# rectifier_schematic.net
KiCad netlist of a schematic drawn in EAGLE
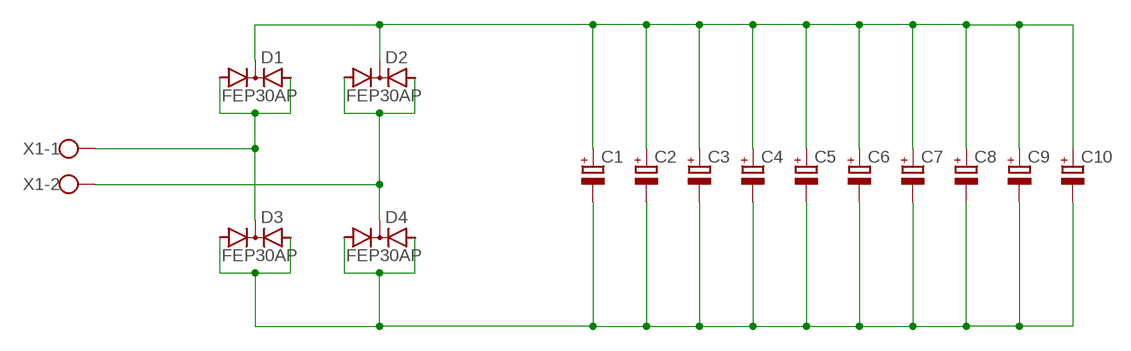
[diagram p0: schematic, sheet 1]

(export (version "E")
  (design (tool "Eeschema 10.0.6"))
  (components
    (comp (ref "C1")
      (value "CPOL-EUE7.5-18")
      (footprint "eagle-import:E7,5-18")
      (libsource (lib "eagle-import") (part "CPOL-EUE7.5-18"))
    )
    (comp (ref "C2")
      (value "CPOL-EUE7.5-18")
      (footprint "eagle-import:E7,5-18")
      (libsource (lib "eagle-import") (part "CPOL-EUE7.5-18"))
    )
    (comp (ref "C3")
      (value "CPOL-EUE7.5-18")
      (footprint "eagle-import:E7,5-18")
      (libsource (lib "eagle-import") (part "CPOL-EUE7.5-18"))
    )
    (comp (ref "C4")
      (value "CPOL-EUE7.5-18")
      (footprint "eagle-import:E7,5-18")
      (libsource (lib "eagle-import") (part "CPOL-EUE7.5-18"))
    )
    (comp (ref "C5")
      (value "CPOL-EUE7.5-18")
      (footprint "eagle-import:E7,5-18")
      (libsource (lib "eagle-import") (part "CPOL-EUE7.5-18"))
    )
    (comp (ref "C6")
      (value "CPOL-EUE7.5-18")
      (footprint "eagle-import:E7,5-18")
      (libsource (lib "eagle-import") (part "CPOL-EUE7.5-18"))
    )
    (comp (ref "C7")
      (value "CPOL-EUE7.5-18")
      (footprint "eagle-import:E7,5-18")
      (libsource (lib "eagle-import") (part "CPOL-EUE7.5-18"))
    )
    (comp (ref "C8")
      (value "CPOL-EUE7.5-18")
      (footprint "eagle-import:E7,5-18")
      (libsource (lib "eagle-import") (part "CPOL-EUE7.5-18"))
    )
    (comp (ref "C9")
      (value "CPOL-EUE7.5-18")
      (footprint "eagle-import:E7,5-18")
      (libsource (lib "eagle-import") (part "CPOL-EUE7.5-18"))
    )
    (comp (ref "C10")
      (value "CPOL-EUE7.5-18")
      (footprint "eagle-import:E7,5-18")
      (libsource (lib "eagle-import") (part "CPOL-EUE7.5-18"))
    )
    (comp (ref "D1")
      (value "FEP30AP")
      (footprint "eagle-import:TO3P")
      (libsource (lib "eagle-import") (part "FEP30AP"))
    )
    (comp (ref "D2")
      (value "FEP30AP")
      (footprint "eagle-import:TO3P")
      (libsource (lib "eagle-import") (part "FEP30AP"))
    )
    (comp (ref "D3")
      (value "FEP30AP")
      (footprint "eagle-import:TO3P")
      (libsource (lib "eagle-import") (part "FEP30AP"))
    )
    (comp (ref "D4")
      (value "FEP30AP")
      (footprint "eagle-import:TO3P")
      (libsource (lib "eagle-import") (part "FEP30AP"))
    )
    (comp (ref "X1")
      (value "W237-102")
      (footprint "eagle-import:W237-102")
      (fields (field (name "MPN") "237-102"))
      (libsource (lib "eagle-import") (part "W237-102"))
    )
  )
  (nets
    (net (code "1") (name "Net-(D1-A1)") (class "Default")
      (node (ref "D1") (pin "1") (pinfunction "A1_1") (pintype "passive"))
      (node (ref "D1") (pin "3") (pinfunction "A2_3") (pintype "passive"))
      (node (ref "D3") (pin "2") (pinfunction "C_2") (pintype "passive"))
      (node (ref "X1") (pin "1") (pinfunction "KL_1") (pintype "passive"))
    )
    (net (code "2") (name "Net-(D1-C)") (class "Default")
      (node (ref "C1") (pin "+") (pinfunction "+_+") (pintype "passive"))
      (node (ref "C10") (pin "+") (pinfunction "+_+") (pintype "passive"))
      (node (ref "C2") (pin "+") (pinfunction "+_+") (pintype "passive"))
      (node (ref "C3") (pin "+") (pinfunction "+_+") (pintype "passive"))
      (node (ref "C4") (pin "+") (pinfunction "+_+") (pintype "passive"))
      (node (ref "C5") (pin "+") (pinfunction "+_+") (pintype "passive"))
      (node (ref "C6") (pin "+") (pinfunction "+_+") (pintype "passive"))
      (node (ref "C7") (pin "+") (pinfunction "+_+") (pintype "passive"))
      (node (ref "C8") (pin "+") (pinfunction "+_+") (pintype "passive"))
      (node (ref "C9") (pin "+") (pinfunction "+_+") (pintype "passive"))
      (node (ref "D1") (pin "2") (pinfunction "C_2") (pintype "passive"))
      (node (ref "D2") (pin "2") (pinfunction "C_2") (pintype "passive"))
    )
    (net (code "3") (name "Net-(D2-A1)") (class "Default")
      (node (ref "D2") (pin "1") (pinfunction "A1_1") (pintype "passive"))
      (node (ref "D2") (pin "3") (pinfunction "A2_3") (pintype "passive"))
      (node (ref "D4") (pin "2") (pinfunction "C_2") (pintype "passive"))
      (node (ref "X1") (pin "2") (pinfunction "KL_2") (pintype "passive"))
    )
    (net (code "4") (name "Net-(D3-A1)") (class "Default")
      (node (ref "C1") (pin "-") (pinfunction "-_-") (pintype "passive"))
      (node (ref "C10") (pin "-") (pinfunction "-_-") (pintype "passive"))
      (node (ref "C2") (pin "-") (pinfunction "-_-") (pintype "passive"))
      (node (ref "C3") (pin "-") (pinfunction "-_-") (pintype "passive"))
      (node (ref "C4") (pin "-") (pinfunction "-_-") (pintype "passive"))
      (node (ref "C5") (pin "-") (pinfunction "-_-") (pintype "passive"))
      (node (ref "C6") (pin "-") (pinfunction "-_-") (pintype "passive"))
      (node (ref "C7") (pin "-") (pinfunction "-_-") (pintype "passive"))
      (node (ref "C8") (pin "-") (pinfunction "-_-") (pintype "passive"))
      (node (ref "C9") (pin "-") (pinfunction "-_-") (pintype "passive"))
      (node (ref "D3") (pin "1") (pinfunction "A1_1") (pintype "passive"))
      (node (ref "D3") (pin "3") (pinfunction "A2_3") (pintype "passive"))
      (node (ref "D4") (pin "1") (pinfunction "A1_1") (pintype "passive"))
      (node (ref "D4") (pin "3") (pinfunction "A2_3") (pintype "passive"))
    )
  )
)
